# Fuse-Board.net
KiCad netlist of a schematic drawn in Altium Designer
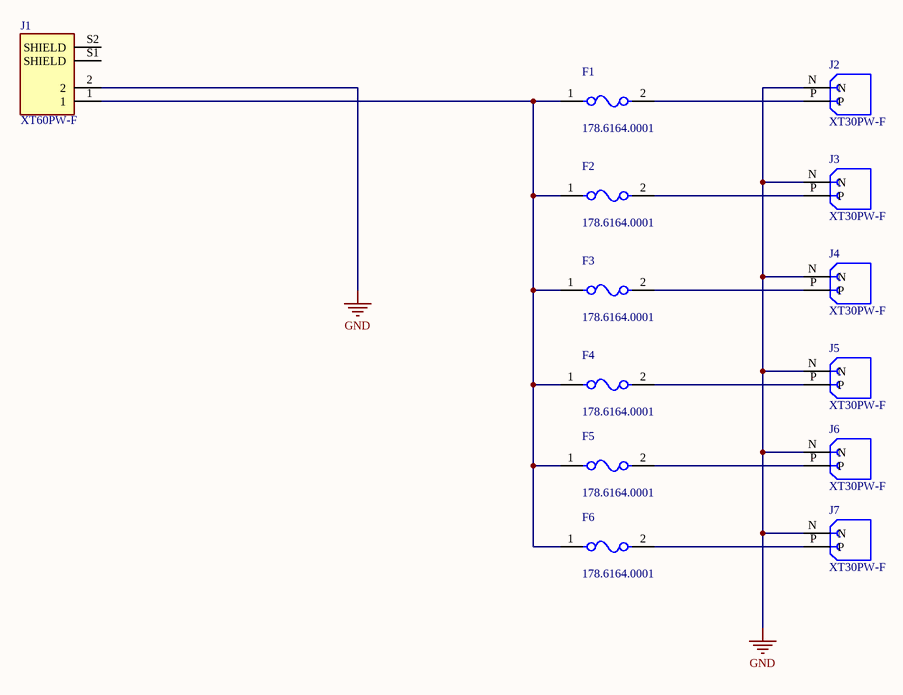
[diagram p0: Fuse-Board.SchDoc]

(export (version "E")
  (design (tool "Eeschema 10.0.6"))
  (components
    (comp (ref "F1")
      (value "178.6164.0001")
      (footprint "FP-178_6164_0001-MFG")
      (description "Fuse Holder  80V 1 Circuit Blade Through Hole")
      (fields (field (name "MANUFACTURER") "Littelfuse Inc"))
      (libsource (lib "Altium Content Vault") (part "5bcf9b9f640e542cf0359d10258e979"))
    )
    (comp (ref "F2")
      (value "178.6164.0001")
      (footprint "FP-178_6164_0001-MFG")
      (description "Fuse Holder  80V 1 Circuit Blade Through Hole")
      (fields (field (name "MANUFACTURER") "Littelfuse Inc"))
      (libsource (lib "Altium Content Vault") (part "5bcf9b9f640e542cf0359d10258e979"))
    )
    (comp (ref "F3")
      (value "178.6164.0001")
      (footprint "FP-178_6164_0001-MFG")
      (description "Fuse Holder  80V 1 Circuit Blade Through Hole")
      (fields (field (name "MANUFACTURER") "Littelfuse Inc"))
      (libsource (lib "Altium Content Vault") (part "5bcf9b9f640e542cf0359d10258e979"))
    )
    (comp (ref "F4")
      (value "178.6164.0001")
      (footprint "FP-178_6164_0001-MFG")
      (description "Fuse Holder  80V 1 Circuit Blade Through Hole")
      (fields (field (name "MANUFACTURER") "Littelfuse Inc"))
      (libsource (lib "Altium Content Vault") (part "5bcf9b9f640e542cf0359d10258e979"))
    )
    (comp (ref "F5")
      (value "178.6164.0001")
      (footprint "FP-178_6164_0001-MFG")
      (description "Fuse Holder  80V 1 Circuit Blade Through Hole")
      (fields (field (name "MANUFACTURER") "Littelfuse Inc"))
      (libsource (lib "Altium Content Vault") (part "5bcf9b9f640e542cf0359d10258e979"))
    )
    (comp (ref "F6")
      (value "178.6164.0001")
      (footprint "FP-178_6164_0001-MFG")
      (description "Fuse Holder  80V 1 Circuit Blade Through Hole")
      (fields (field (name "MANUFACTURER") "Littelfuse Inc"))
      (libsource (lib "Altium Content Vault") (part "5bcf9b9f640e542cf0359d10258e979"))
    )
    (comp (ref "J1")
      (value "XT60PW-F")
      (footprint "AMASS_XT60PW-F")
      (description "Socket DC Supply Connector Female")
      (fields (field (name "MF") "AMASS"))
      (libsource (lib "XT60PW-F") (part "XT60PW-F"))
    )
    (comp (ref "J2")
      (value "XT30PW-F")
      (footprint "AMASS_XT30PW-F")
      (description "Socket; DC supply; XT30; female; PIN: 2; on PCBs; THT; yellow; 15A")
      (fields (field (name "MF") "amass"))
      (libsource (lib "XT30PW-F") (part "XT30PW-F"))
    )
    (comp (ref "J3")
      (value "XT30PW-F")
      (footprint "AMASS_XT30PW-F")
      (description "Socket; DC supply; XT30; female; PIN: 2; on PCBs; THT; yellow; 15A")
      (fields (field (name "MF") "amass"))
      (libsource (lib "XT30PW-F") (part "XT30PW-F"))
    )
    (comp (ref "J4")
      (value "XT30PW-F")
      (footprint "AMASS_XT30PW-F")
      (description "Socket; DC supply; XT30; female; PIN: 2; on PCBs; THT; yellow; 15A")
      (fields (field (name "MF") "amass"))
      (libsource (lib "XT30PW-F") (part "XT30PW-F"))
    )
    (comp (ref "J5")
      (value "XT30PW-F")
      (footprint "AMASS_XT30PW-F")
      (description "Socket; DC supply; XT30; female; PIN: 2; on PCBs; THT; yellow; 15A")
      (fields (field (name "MF") "amass"))
      (libsource (lib "XT30PW-F") (part "XT30PW-F"))
    )
    (comp (ref "J6")
      (value "XT30PW-F")
      (footprint "AMASS_XT30PW-F")
      (description "Socket; DC supply; XT30; female; PIN: 2; on PCBs; THT; yellow; 15A")
      (fields (field (name "MF") "amass"))
      (libsource (lib "XT30PW-F") (part "XT30PW-F"))
    )
    (comp (ref "J7")
      (value "XT30PW-F")
      (footprint "AMASS_XT30PW-F")
      (description "Socket; DC supply; XT30; female; PIN: 2; on PCBs; THT; yellow; 15A")
      (fields (field (name "MF") "amass"))
      (libsource (lib "XT30PW-F") (part "XT30PW-F"))
    )
  )
  (nets
    (net (code "1") (name "GND") (class "Default")
      (node (ref "J1") (pin "2") (pinfunction "2_2") (pintype "passive"))
      (node (ref "J2") (pin "N") (pinfunction "N_N") (pintype "power_in"))
      (node (ref "J3") (pin "N") (pinfunction "N_N") (pintype "power_in"))
      (node (ref "J4") (pin "N") (pinfunction "N_N") (pintype "power_in"))
      (node (ref "J5") (pin "N") (pinfunction "N_N") (pintype "power_in"))
      (node (ref "J6") (pin "N") (pinfunction "N_N") (pintype "power_in"))
      (node (ref "J7") (pin "N") (pinfunction "N_N") (pintype "power_in"))
    )
    (net (code "2") (name "Net-(F1-Pad1)") (class "Default")
      (node (ref "F1") (pin "1") (pinfunction "1_1") (pintype "passive"))
      (node (ref "F2") (pin "1") (pinfunction "1_1") (pintype "passive"))
      (node (ref "F3") (pin "1") (pinfunction "1_1") (pintype "passive"))
      (node (ref "F4") (pin "1") (pinfunction "1_1") (pintype "passive"))
      (node (ref "F5") (pin "1") (pinfunction "1_1") (pintype "passive"))
      (node (ref "F6") (pin "1") (pinfunction "1_1") (pintype "passive"))
      (node (ref "J1") (pin "1") (pinfunction "1_1") (pintype "passive"))
    )
    (net (code "3") (name "Net-(F1-Pad2)") (class "Default")
      (node (ref "F1") (pin "2") (pinfunction "2_2") (pintype "passive"))
      (node (ref "J2") (pin "P") (pinfunction "P_P") (pintype "power_in"))
    )
    (net (code "4") (name "Net-(F2-Pad2)") (class "Default")
      (node (ref "F2") (pin "2") (pinfunction "2_2") (pintype "passive"))
      (node (ref "J3") (pin "P") (pinfunction "P_P") (pintype "power_in"))
    )
    (net (code "5") (name "Net-(F3-Pad2)") (class "Default")
      (node (ref "F3") (pin "2") (pinfunction "2_2") (pintype "passive"))
      (node (ref "J4") (pin "P") (pinfunction "P_P") (pintype "power_in"))
    )
    (net (code "6") (name "Net-(F4-Pad2)") (class "Default")
      (node (ref "F4") (pin "2") (pinfunction "2_2") (pintype "passive"))
      (node (ref "J5") (pin "P") (pinfunction "P_P") (pintype "power_in"))
    )
    (net (code "7") (name "Net-(F5-Pad2)") (class "Default")
      (node (ref "F5") (pin "2") (pinfunction "2_2") (pintype "passive"))
      (node (ref "J6") (pin "P") (pinfunction "P_P") (pintype "power_in"))
    )
    (net (code "8") (name "Net-(F6-Pad2)") (class "Default")
      (node (ref "F6") (pin "2") (pinfunction "2_2") (pintype "passive"))
      (node (ref "J7") (pin "P") (pinfunction "P_P") (pintype "power_in"))
    )
    (net (code "9") (name "unconnected-(J1-SHIELD-PadS1)") (class "Default")
      (node (ref "J1") (pin "S1") (pinfunction "SHIELD_S1") (pintype "passive"))
    )
    (net (code "10") (name "unconnected-(J1-SHIELD-PadS2)") (class "Default")
      (node (ref "J1") (pin "S2") (pinfunction "SHIELD_S2") (pintype "passive"))
    )
  )
)
